# ScopeMag.net
KiCad netlist of a schematic drawn in Altium Designer
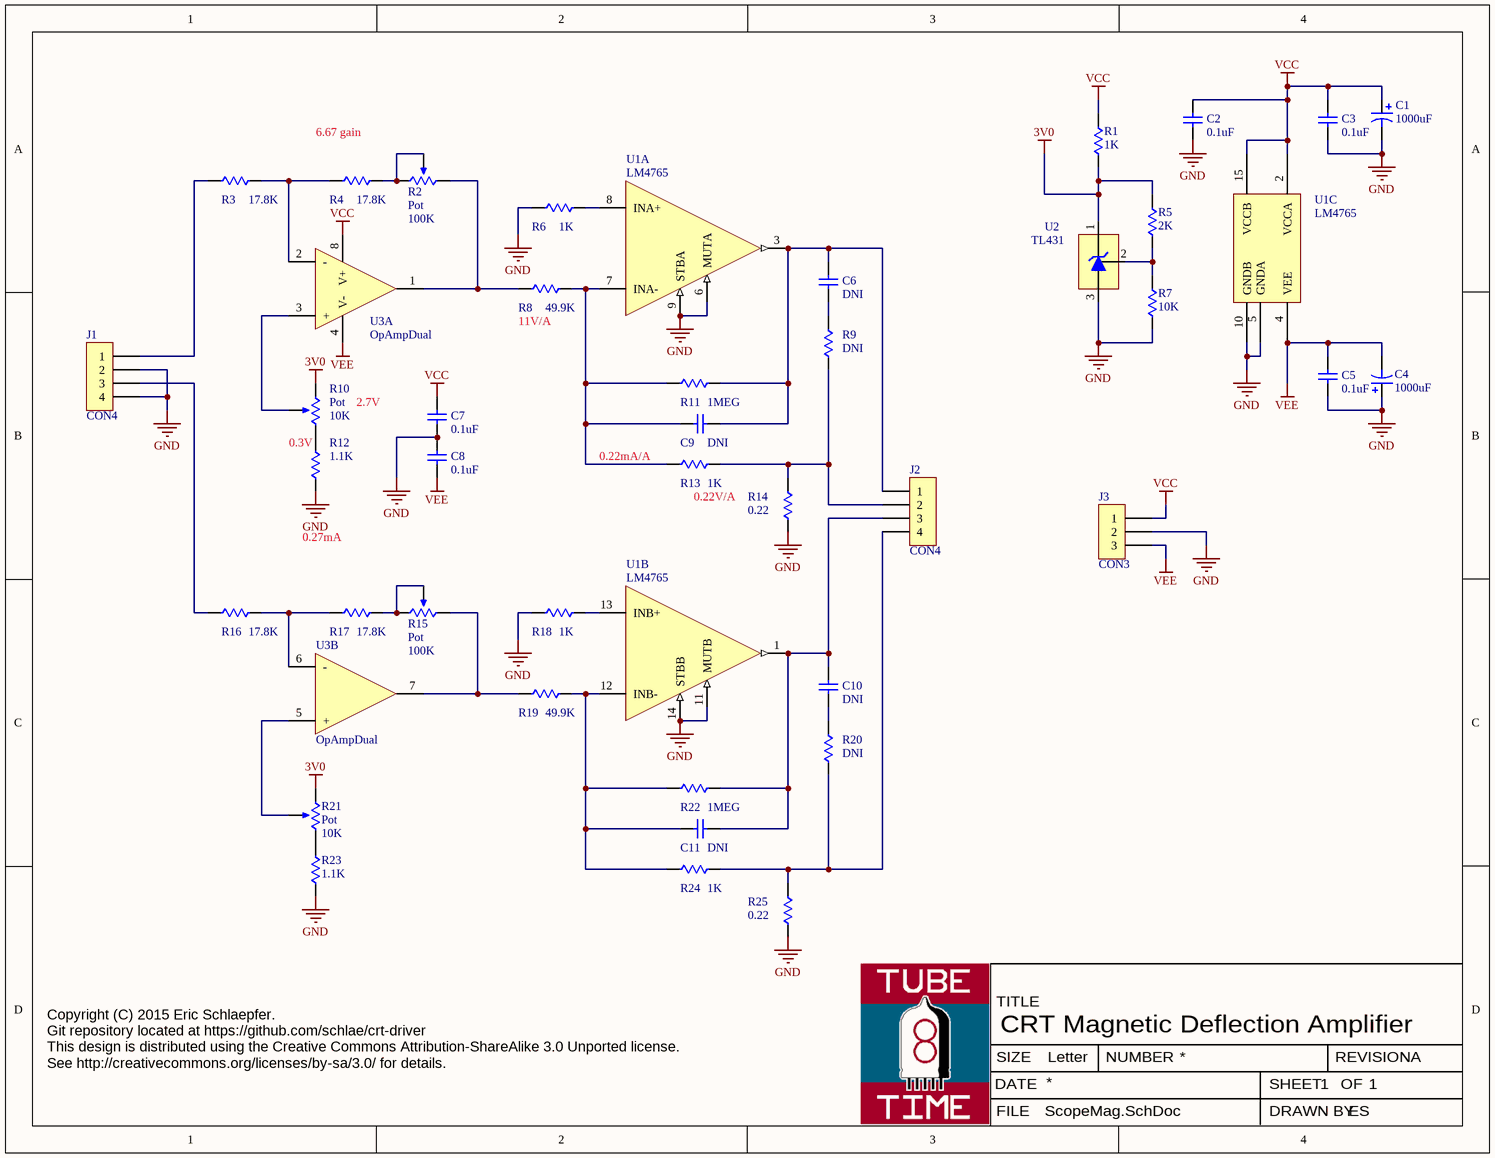
[diagram p0: ScopeMag.SchDoc]

(export (version "E")
  (design (tool "Eeschema 10.0.6"))
  (components
    (comp (ref "C1")
      (value "1000uF")
      (footprint "CAP_R200x400")
      (description "Polarized Capacitor")
      (fields (field (name "MANUFPART") "UVR1E102MPD") (field (name "Comment") "Cap Pol2"))
      (libsource (lib "ClikCommon") (part "CapP"))
    )
    (comp (ref "C2")
      (value "0.1uF")
      (footprint "G_0805[2012]")
      (description "Capacitor")
      (fields (field (name "Comment") "Cap"))
      (libsource (lib "ClikCommon") (part "Cap"))
    )
    (comp (ref "C3")
      (value "0.1uF")
      (footprint "G_0805[2012]")
      (description "Capacitor")
      (fields (field (name "Comment") "Cap"))
      (libsource (lib "ClikCommon") (part "Cap"))
    )
    (comp (ref "C4")
      (value "1000uF")
      (footprint "CAP_R200x400")
      (description "Polarized Capacitor")
      (fields (field (name "MANUFPART") "UVR1E102MPD") (field (name "Comment") "Cap Pol2"))
      (libsource (lib "ClikCommon") (part "CapP"))
    )
    (comp (ref "C5")
      (value "0.1uF")
      (footprint "G_0805[2012]")
      (description "Capacitor")
      (fields (field (name "Comment") "Cap"))
      (libsource (lib "ClikCommon") (part "Cap"))
    )
    (comp (ref "C6")
      (value "DNI")
      (footprint "G_0805[2012]")
      (description "Capacitor")
      (fields (field (name "Comment") "Cap"))
      (libsource (lib "ClikCommon") (part "Cap"))
    )
    (comp (ref "C7")
      (value "0.1uF")
      (footprint "G_0805[2012]")
      (description "Capacitor")
      (fields (field (name "Comment") "Cap"))
      (libsource (lib "ClikCommon") (part "Cap"))
    )
    (comp (ref "C8")
      (value "0.1uF")
      (footprint "G_0805[2012]")
      (description "Capacitor")
      (fields (field (name "Comment") "Cap"))
      (libsource (lib "ClikCommon") (part "Cap"))
    )
    (comp (ref "C9")
      (value "DNI")
      (footprint "G_0805[2012]")
      (description "Capacitor")
      (fields (field (name "Comment") "Cap"))
      (libsource (lib "ClikCommon") (part "Cap"))
    )
    (comp (ref "C10")
      (value "DNI")
      (footprint "G_0805[2012]")
      (description "Capacitor")
      (fields (field (name "Comment") "Cap"))
      (libsource (lib "ClikCommon") (part "Cap"))
    )
    (comp (ref "C11")
      (value "DNI")
      (footprint "G_0805[2012]")
      (description "Capacitor")
      (fields (field (name "Comment") "Cap"))
      (libsource (lib "ClikCommon") (part "Cap"))
    )
    (comp (ref "J1")
      (value "CON4")
      (footprint "HDR4S")
      (description "Connector, 4 pin")
      (fields (field (name "MANUFPART") "42375-1863"))
      (libsource (lib "ClikConnectors") (part "CON4"))
    )
    (comp (ref "J2")
      (value "CON4")
      (footprint "HDR4S156")
      (description "Connector, 4 pin")
      (fields (field (name "MANUFPART") "26-48-1041"))
      (libsource (lib "") (part "CON4_1"))
    )
    (comp (ref "J3")
      (value "CON3")
      (footprint "HDR3S156")
      (description "Connector, 3 pin")
      (fields (field (name "MANUFPART") "26-48-1031"))
      (libsource (lib "ClikConnectors") (part "CON3"))
    )
    (comp (ref "R1")
      (value "1K")
      (footprint "G_0805[2012]")
      (description "Resistor")
      (fields (field (name "Comment") "Res1"))
      (libsource (lib "ClikCommon") (part "Res"))
    )
    (comp (ref "R2")
      (value "Pot")
      (footprint "POT_TRIM BOURNS 3386F")
      (description "Variable Resistor")
      (fields (field (name "ALTIUM_VALUE") "100K"))
      (libsource (lib "ClikCommon") (part "Pot"))
    )
    (comp (ref "R3")
      (value "17.8K")
      (footprint "G_0805[2012]")
      (description "Resistor")
      (fields (field (name "Comment") "Res1"))
      (libsource (lib "ClikCommon") (part "Res"))
    )
    (comp (ref "R4")
      (value "17.8K")
      (footprint "G_0805[2012]")
      (description "Resistor")
      (fields (field (name "Comment") "Res1"))
      (libsource (lib "ClikCommon") (part "Res"))
    )
    (comp (ref "R5")
      (value "2K")
      (footprint "G_0805[2012]")
      (description "Resistor")
      (fields (field (name "Comment") "Res1"))
      (libsource (lib "ClikCommon") (part "Res"))
    )
    (comp (ref "R6")
      (value "1K")
      (footprint "G_0805[2012]")
      (description "Resistor")
      (fields (field (name "Comment") "Res1"))
      (libsource (lib "ClikCommon") (part "Res"))
    )
    (comp (ref "R7")
      (value "10K")
      (footprint "G_0805[2012]")
      (description "Resistor")
      (fields (field (name "Comment") "Res1"))
      (libsource (lib "ClikCommon") (part "Res"))
    )
    (comp (ref "R8")
      (value "49.9K")
      (footprint "G_0805[2012]")
      (description "Resistor")
      (fields (field (name "Comment") "Res1"))
      (libsource (lib "ClikCommon") (part "Res"))
    )
    (comp (ref "R9")
      (value "DNI")
      (footprint "G_0805[2012]")
      (description "Resistor")
      (fields (field (name "Comment") "Res1"))
      (libsource (lib "ClikCommon") (part "Res"))
    )
    (comp (ref "R10")
      (value "Pot")
      (footprint "POT_TRIM BOURNS 3386F")
      (description "Variable Resistor")
      (fields (field (name "ALTIUM_VALUE") "10K"))
      (libsource (lib "ClikCommon") (part "Pot"))
    )
    (comp (ref "R11")
      (value "1MEG")
      (footprint "G_0805[2012]")
      (description "Resistor")
      (fields (field (name "Comment") "Res1"))
      (libsource (lib "ClikCommon") (part "Res"))
    )
    (comp (ref "R12")
      (value "1.1K")
      (footprint "G_0805[2012]")
      (description "Resistor")
      (fields (field (name "Comment") "Res1"))
      (libsource (lib "ClikCommon") (part "Res"))
    )
    (comp (ref "R13")
      (value "1K")
      (footprint "G_0805[2012]")
      (description "Resistor")
      (fields (field (name "Comment") "Res1"))
      (libsource (lib "ClikCommon") (part "Res"))
    )
    (comp (ref "R14")
      (value "0.22")
      (footprint "G_2512")
      (description "Resistor")
      (fields (field (name "Comment") "Res1"))
      (libsource (lib "ClikCommon") (part "Res"))
    )
    (comp (ref "R15")
      (value "Pot")
      (footprint "POT_TRIM BOURNS 3386F")
      (description "Variable Resistor")
      (fields (field (name "ALTIUM_VALUE") "100K"))
      (libsource (lib "ClikCommon") (part "Pot"))
    )
    (comp (ref "R16")
      (value "17.8K")
      (footprint "G_0805[2012]")
      (description "Resistor")
      (fields (field (name "Comment") "Res1"))
      (libsource (lib "ClikCommon") (part "Res"))
    )
    (comp (ref "R17")
      (value "17.8K")
      (footprint "G_0805[2012]")
      (description "Resistor")
      (fields (field (name "Comment") "Res1"))
      (libsource (lib "ClikCommon") (part "Res"))
    )
    (comp (ref "R18")
      (value "1K")
      (footprint "G_0805[2012]")
      (description "Resistor")
      (fields (field (name "Comment") "Res1"))
      (libsource (lib "ClikCommon") (part "Res"))
    )
    (comp (ref "R19")
      (value "49.9K")
      (footprint "G_0805[2012]")
      (description "Resistor")
      (fields (field (name "Comment") "Res1"))
      (libsource (lib "ClikCommon") (part "Res"))
    )
    (comp (ref "R20")
      (value "DNI")
      (footprint "G_0805[2012]")
      (description "Resistor")
      (fields (field (name "Comment") "Res1"))
      (libsource (lib "ClikCommon") (part "Res"))
    )
    (comp (ref "R21")
      (value "Pot")
      (footprint "POT_TRIM BOURNS 3386F")
      (description "Variable Resistor")
      (fields (field (name "ALTIUM_VALUE") "10K"))
      (libsource (lib "ClikCommon") (part "Pot"))
    )
    (comp (ref "R22")
      (value "1MEG")
      (footprint "G_0805[2012]")
      (description "Resistor")
      (fields (field (name "Comment") "Res1"))
      (libsource (lib "ClikCommon") (part "Res"))
    )
    (comp (ref "R23")
      (value "1.1K")
      (footprint "G_0805[2012]")
      (description "Resistor")
      (fields (field (name "Comment") "Res1"))
      (libsource (lib "ClikCommon") (part "Res"))
    )
    (comp (ref "R24")
      (value "1K")
      (footprint "G_0805[2012]")
      (description "Resistor")
      (fields (field (name "Comment") "Res1"))
      (libsource (lib "ClikCommon") (part "Res"))
    )
    (comp (ref "R25")
      (value "0.22")
      (footprint "G_2512")
      (description "Resistor")
      (fields (field (name "Comment") "Res1"))
      (libsource (lib "ClikCommon") (part "Res"))
    )
    (comp (ref "U1") (value "LM4765") (footprint "LM4765") (libsource (lib "ClikIC") (part "LM4765")))
    (comp (ref "U2")
      (value "TL431")
      (footprint "G_SOT23")
      (description "Adjustable Shunt Reg")
      (libsource (lib "ClikIC") (part "TL431"))
    )
    (comp (ref "U3")
      (value "OpAmpDual")
      (footprint "G_SO8")
      (description "Generic Dual Op Amp")
      (libsource (lib "ClikIC") (part "OpAmpDual"))
    )
  )
  (nets
    (net (code "1") (name "3V0") (class "Default")
      (node (ref "R1") (pin "2") (pinfunction "2_2") (pintype "passive"))
      (node (ref "R10") (pin "1") (pinfunction "TOP_1") (pintype "passive"))
      (node (ref "R21") (pin "1") (pinfunction "TOP_1") (pintype "passive"))
      (node (ref "R5") (pin "1") (pinfunction "1_1") (pintype "passive"))
      (node (ref "U2") (pin "1") (pinfunction "C_1") (pintype "passive"))
    )
    (net (code "2") (name "GND") (class "Default")
      (node (ref "C1") (pin "2") (pinfunction "2_2") (pintype "passive"))
      (node (ref "C2") (pin "1") (pinfunction "1_1") (pintype "passive"))
      (node (ref "C3") (pin "1") (pinfunction "1_1") (pintype "passive"))
      (node (ref "C4") (pin "1") (pinfunction "1_1") (pintype "passive"))
      (node (ref "C5") (pin "1") (pinfunction "1_1") (pintype "passive"))
      (node (ref "C7") (pin "1") (pinfunction "1_1") (pintype "passive"))
      (node (ref "C8") (pin "2") (pinfunction "2_2") (pintype "passive"))
      (node (ref "J1") (pin "2") (pinfunction "2_2") (pintype "passive"))
      (node (ref "J1") (pin "4") (pinfunction "4_4") (pintype "passive"))
      (node (ref "J3") (pin "2") (pinfunction "2_2") (pintype "passive"))
      (node (ref "R12") (pin "2") (pinfunction "2_2") (pintype "passive"))
      (node (ref "R14") (pin "2") (pinfunction "2_2") (pintype "passive"))
      (node (ref "R18") (pin "1") (pinfunction "1_1") (pintype "passive"))
      (node (ref "R23") (pin "2") (pinfunction "2_2") (pintype "passive"))
      (node (ref "R25") (pin "2") (pinfunction "2_2") (pintype "passive"))
      (node (ref "R6") (pin "1") (pinfunction "1_1") (pintype "passive"))
      (node (ref "R7") (pin "2") (pinfunction "2_2") (pintype "passive"))
      (node (ref "U1") (pin "10") (pinfunction "GNDB_10") (pintype "power_in"))
      (node (ref "U1") (pin "11") (pinfunction "MUTB_11") (pintype "input"))
      (node (ref "U1") (pin "14") (pinfunction "STBB_14") (pintype "input"))
      (node (ref "U1") (pin "5") (pinfunction "GNDA_5") (pintype "power_in"))
      (node (ref "U1") (pin "6") (pinfunction "MUTA_6") (pintype "input"))
      (node (ref "U1") (pin "9") (pinfunction "STBA_9") (pintype "input"))
      (node (ref "U2") (pin "3") (pinfunction "A_3") (pintype "passive"))
    )
    (net (code "3") (name "Net-(C6-Pad1)") (class "Default")
      (node (ref "C6") (pin "1") (pinfunction "1_1") (pintype "passive"))
      (node (ref "R9") (pin "1") (pinfunction "1_1") (pintype "passive"))
    )
    (net (code "4") (name "Net-(C10-Pad1)") (class "Default")
      (node (ref "C10") (pin "1") (pinfunction "1_1") (pintype "passive"))
      (node (ref "R20") (pin "1") (pinfunction "1_1") (pintype "passive"))
    )
    (net (code "5") (name "Net-(J1-Pad1)") (class "Default")
      (node (ref "J1") (pin "1") (pinfunction "1_1") (pintype "passive"))
      (node (ref "R3") (pin "1") (pinfunction "1_1") (pintype "passive"))
    )
    (net (code "6") (name "Net-(J1-Pad3)") (class "Default")
      (node (ref "J1") (pin "3") (pinfunction "3_3") (pintype "passive"))
      (node (ref "R16") (pin "1") (pinfunction "1_1") (pintype "passive"))
    )
    (net (code "7") (name "Net-(J2-Pad2)") (class "Default")
      (node (ref "J2") (pin "2") (pinfunction "2_2") (pintype "passive"))
      (node (ref "R13") (pin "2") (pinfunction "2_2") (pintype "passive"))
      (node (ref "R14") (pin "1") (pinfunction "1_1") (pintype "passive"))
      (node (ref "R9") (pin "2") (pinfunction "2_2") (pintype "passive"))
    )
    (net (code "8") (name "Net-(J2-Pad4)") (class "Default")
      (node (ref "J2") (pin "4") (pinfunction "4_4") (pintype "passive"))
      (node (ref "R20") (pin "2") (pinfunction "2_2") (pintype "passive"))
      (node (ref "R24") (pin "2") (pinfunction "2_2") (pintype "passive"))
      (node (ref "R25") (pin "1") (pinfunction "1_1") (pintype "passive"))
    )
    (net (code "9") (name "Net-(R2-BOT)") (class "Default")
      (node (ref "R2") (pin "2") (pinfunction "BOT_2") (pintype "passive"))
      (node (ref "R2") (pin "3") (pinfunction "TAP_3") (pintype "passive"))
      (node (ref "R4") (pin "2") (pinfunction "2_2") (pintype "passive"))
    )
    (net (code "10") (name "Net-(R2-TOP)") (class "Default")
      (node (ref "R2") (pin "1") (pinfunction "TOP_1") (pintype "passive"))
      (node (ref "R8") (pin "1") (pinfunction "1_1") (pintype "passive"))
      (node (ref "U3") (pin "1") (pinfunction "OUTA_1") (pintype "passive"))
    )
    (net (code "11") (name "Net-(R10-BOT)") (class "Default")
      (node (ref "R10") (pin "2") (pinfunction "BOT_2") (pintype "passive"))
      (node (ref "R12") (pin "1") (pinfunction "1_1") (pintype "passive"))
    )
    (net (code "12") (name "Net-(R10-TAP)") (class "Default")
      (node (ref "R10") (pin "3") (pinfunction "TAP_3") (pintype "passive"))
      (node (ref "U3") (pin "3") (pinfunction "+_3") (pintype "passive"))
    )
    (net (code "13") (name "Net-(R15-BOT)") (class "Default")
      (node (ref "R15") (pin "2") (pinfunction "BOT_2") (pintype "passive"))
      (node (ref "R15") (pin "3") (pinfunction "TAP_3") (pintype "passive"))
      (node (ref "R17") (pin "2") (pinfunction "2_2") (pintype "passive"))
    )
    (net (code "14") (name "Net-(R15-TOP)") (class "Default")
      (node (ref "R15") (pin "1") (pinfunction "TOP_1") (pintype "passive"))
      (node (ref "R19") (pin "1") (pinfunction "1_1") (pintype "passive"))
      (node (ref "U3") (pin "7") (pinfunction "OUTB_7") (pintype "passive"))
    )
    (net (code "15") (name "Net-(R21-BOT)") (class "Default")
      (node (ref "R21") (pin "2") (pinfunction "BOT_2") (pintype "passive"))
      (node (ref "R23") (pin "1") (pinfunction "1_1") (pintype "passive"))
    )
    (net (code "16") (name "Net-(R21-TAP)") (class "Default")
      (node (ref "R21") (pin "3") (pinfunction "TAP_3") (pintype "passive"))
      (node (ref "U3") (pin "5") (pinfunction "+_5") (pintype "passive"))
    )
    (net (code "17") (name "Net-(U1A-INA+)") (class "Default")
      (node (ref "R6") (pin "2") (pinfunction "2_2") (pintype "passive"))
      (node (ref "U1") (pin "8") (pinfunction "INA+_8") (pintype "passive"))
    )
    (net (code "18") (name "Net-(U1A-INA-)") (class "Default")
      (node (ref "C9") (pin "2") (pinfunction "2_2") (pintype "passive"))
      (node (ref "R11") (pin "1") (pinfunction "1_1") (pintype "passive"))
      (node (ref "R13") (pin "1") (pinfunction "1_1") (pintype "passive"))
      (node (ref "R8") (pin "2") (pinfunction "2_2") (pintype "passive"))
      (node (ref "U1") (pin "7") (pinfunction "INA-_7") (pintype "passive"))
    )
    (net (code "19") (name "Net-(U1A-OUTA)") (class "Default")
      (node (ref "C6") (pin "2") (pinfunction "2_2") (pintype "passive"))
      (node (ref "C9") (pin "1") (pinfunction "1_1") (pintype "passive"))
      (node (ref "J2") (pin "1") (pinfunction "1_1") (pintype "passive"))
      (node (ref "R11") (pin "2") (pinfunction "2_2") (pintype "passive"))
      (node (ref "U1") (pin "3") (pinfunction "OUTA_3") (pintype "output"))
    )
    (net (code "20") (name "Net-(U1B-INB+)") (class "Default")
      (node (ref "R18") (pin "2") (pinfunction "2_2") (pintype "passive"))
      (node (ref "U1") (pin "13") (pinfunction "INB+_13") (pintype "passive"))
    )
    (net (code "21") (name "Net-(U1B-INB-)") (class "Default")
      (node (ref "C11") (pin "2") (pinfunction "2_2") (pintype "passive"))
      (node (ref "R19") (pin "2") (pinfunction "2_2") (pintype "passive"))
      (node (ref "R22") (pin "1") (pinfunction "1_1") (pintype "passive"))
      (node (ref "R24") (pin "1") (pinfunction "1_1") (pintype "passive"))
      (node (ref "U1") (pin "12") (pinfunction "INB-_12") (pintype "passive"))
    )
    (net (code "22") (name "Net-(U1B-OUTB)") (class "Default")
      (node (ref "C10") (pin "2") (pinfunction "2_2") (pintype "passive"))
      (node (ref "C11") (pin "1") (pinfunction "1_1") (pintype "passive"))
      (node (ref "J2") (pin "3") (pinfunction "3_3") (pintype "passive"))
      (node (ref "R22") (pin "2") (pinfunction "2_2") (pintype "passive"))
      (node (ref "U1") (pin "1") (pinfunction "OUTB_1") (pintype "output"))
    )
    (net (code "23") (name "Net-(U2-REF)") (class "Default")
      (node (ref "R5") (pin "2") (pinfunction "2_2") (pintype "passive"))
      (node (ref "R7") (pin "1") (pinfunction "1_1") (pintype "passive"))
      (node (ref "U2") (pin "2") (pinfunction "REF_2") (pintype "passive"))
    )
    (net (code "24") (name "Net-(U3A--)") (class "Default")
      (node (ref "R3") (pin "2") (pinfunction "2_2") (pintype "passive"))
      (node (ref "R4") (pin "1") (pinfunction "1_1") (pintype "passive"))
      (node (ref "U3") (pin "2") (pinfunction "-_2") (pintype "passive"))
    )
    (net (code "25") (name "Net-(U3B--)") (class "Default")
      (node (ref "R16") (pin "2") (pinfunction "2_2") (pintype "passive"))
      (node (ref "R17") (pin "1") (pinfunction "1_1") (pintype "passive"))
      (node (ref "U3") (pin "6") (pinfunction "-_6") (pintype "passive"))
    )
    (net (code "26") (name "VCC") (class "Default")
      (node (ref "C1") (pin "1") (pinfunction "1_1") (pintype "passive"))
      (node (ref "C2") (pin "2") (pinfunction "2_2") (pintype "passive"))
      (node (ref "C3") (pin "2") (pinfunction "2_2") (pintype "passive"))
      (node (ref "C7") (pin "2") (pinfunction "2_2") (pintype "passive"))
      (node (ref "J3") (pin "1") (pinfunction "1_1") (pintype "passive"))
      (node (ref "R1") (pin "1") (pinfunction "1_1") (pintype "passive"))
      (node (ref "U1") (pin "15") (pinfunction "VCCB_15") (pintype "power_in"))
      (node (ref "U1") (pin "2") (pinfunction "VCCA_2") (pintype "power_in"))
      (node (ref "U3") (pin "8") (pinfunction "V+_8") (pintype "power_in"))
    )
    (net (code "27") (name "VEE") (class "Default")
      (node (ref "C4") (pin "2") (pinfunction "2_2") (pintype "passive"))
      (node (ref "C5") (pin "2") (pinfunction "2_2") (pintype "passive"))
      (node (ref "C8") (pin "1") (pinfunction "1_1") (pintype "passive"))
      (node (ref "J3") (pin "3") (pinfunction "3_3") (pintype "passive"))
      (node (ref "U1") (pin "4") (pinfunction "VEE_4") (pintype "power_in"))
      (node (ref "U3") (pin "4") (pinfunction "V-_4") (pintype "power_in"))
    )
  )
)
